# Output.net
KiCad netlist of a schematic drawn in Altium Designer
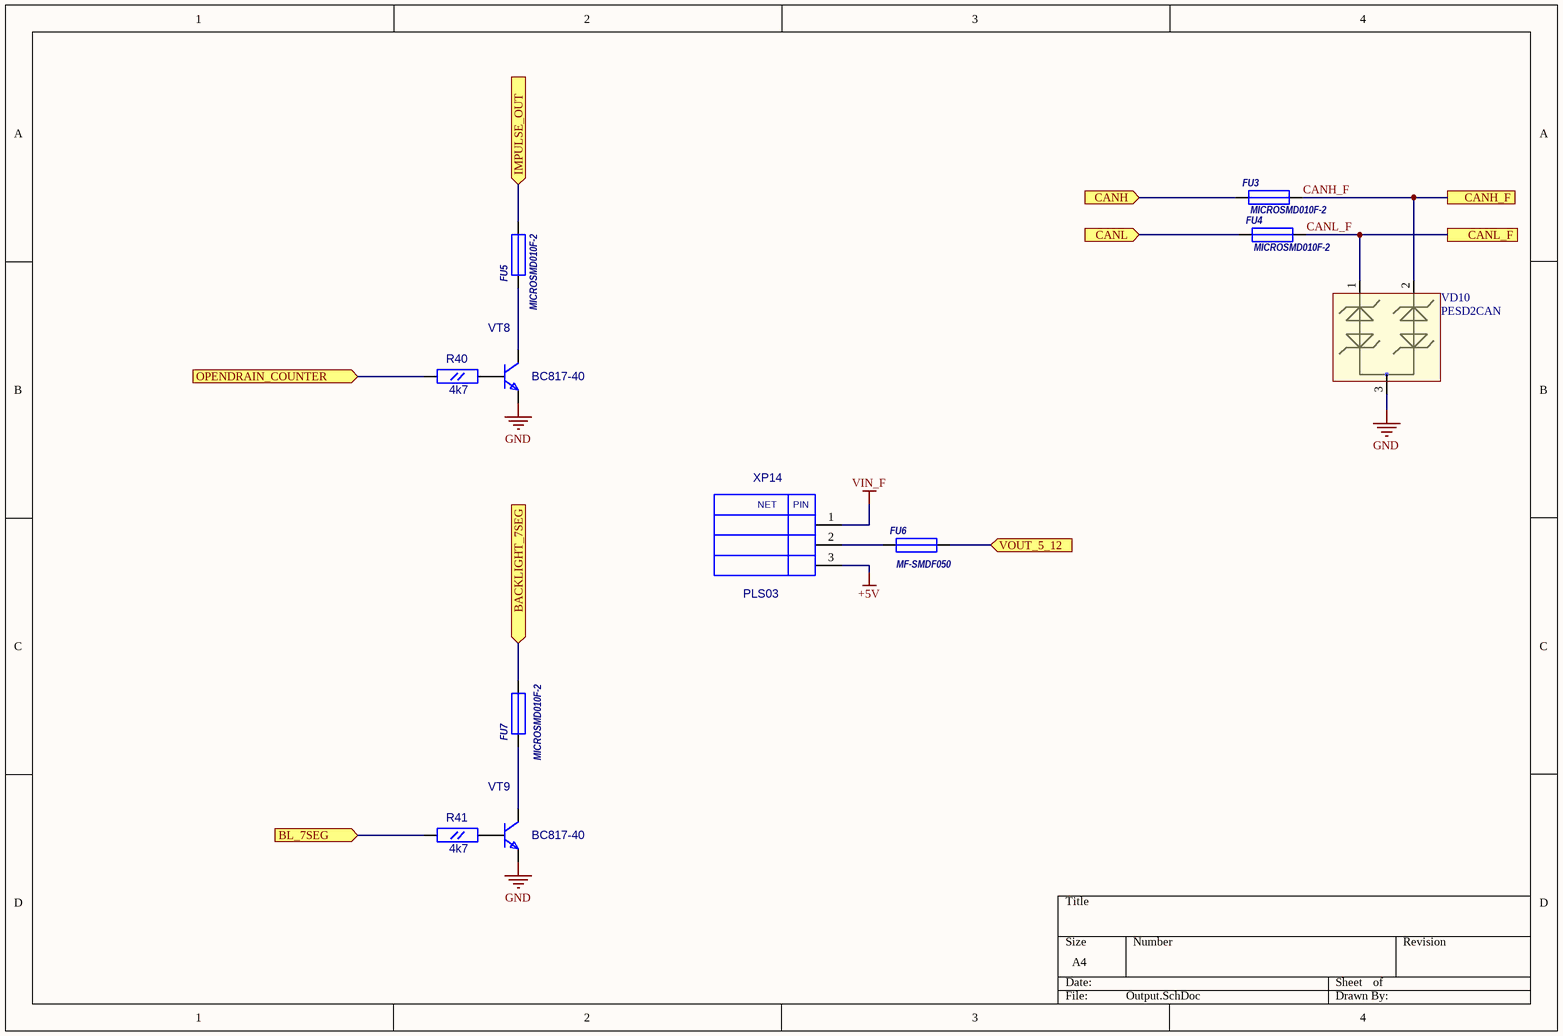
[diagram p0: Output.SchDoc]

(export (version "E")
  (design (tool "Eeschema 10.0.6"))
  (components
    (comp (ref "FU3")
      (value "MICROSMD010F-2")
      (footprint "RC1210")
      (description "MICROSMD")
      (libsource (lib "gprs_modem_2") (part "MICROSMD"))
    )
    (comp (ref "FU4")
      (value "MICROSMD010F-2")
      (footprint "RC1210")
      (description "MICROSMD")
      (libsource (lib "gprs_modem_2") (part "MICROSMD"))
    )
    (comp (ref "FU5")
      (value "MICROSMD010F-2")
      (footprint "RC1210")
      (description "MICROSMD")
      (libsource (lib "gprs_modem_2") (part "MICROSMD"))
    )
    (comp (ref "FU6")
      (value "MF-SMDF050")
      (footprint "MF-SMDF")
      (description "MF-SMDF")
      (libsource (lib "gprs_modem_2") (part "MF-SMDF"))
    )
    (comp (ref "FU7")
      (value "MICROSMD010F-2")
      (footprint "RC1210")
      (description "MICROSMD")
      (libsource (lib "gprs_modem_2") (part "MICROSMD"))
    )
    (comp (ref "R40")
      (value "4k7")
      (footprint "RC0603")
      (description "RC0603")
      (libsource (lib "gprs_modem_2") (part "RC0603"))
    )
    (comp (ref "R41")
      (value "4k7")
      (footprint "RC0603")
      (description "RC0603")
      (libsource (lib "gprs_modem_2") (part "RC0603"))
    )
    (comp (ref "VD10")
      (value "PESD2CAN")
      (footprint "SOT-23(123)")
      (description "TVS for CAN")
      (libsource (lib "gprs_modem_2") (part "PESD2CAN"))
    )
    (comp (ref "VT8")
      (value "BC817-40")
      (footprint "SOT-23(123)")
      (description "NPN 500ma transistor")
      (libsource (lib "gprs_modem_2") (part "BC846BLT1"))
    )
    (comp (ref "VT9")
      (value "BC817-40")
      (footprint "SOT-23(123)")
      (description "NPN 500ma transistor")
      (libsource (lib "gprs_modem_2") (part "BC846BLT1"))
    )
    (comp (ref "XP14") (value "PLS03") (footprint "PLS-03") (libsource (lib "gprs_modem_2") (part "PLS03")))
  )
  (nets
    (net (code "1") (name "+5V") (class "Default")
      (node (ref "XP14") (pin "3") (pinfunction "3_3") (pintype "passive"))
    )
    (net (code "2") (name "/BACKLIGHT_7SEG") (class "Default")
      (node (ref "FU7") (pin "2") (pintype "passive"))
    )
    (net (code "3") (name "/BL_7SEG") (class "Default")
      (node (ref "R41") (pin "1") (pinfunction "A_1") (pintype "passive"))
    )
    (net (code "4") (name "/CANH") (class "Default") (node (ref "FU3") (pin "1") (pintype "passive")))
    (net (code "5") (name "/CANH_F") (class "Default")
      (node (ref "FU3") (pin "2") (pintype "passive"))
      (node (ref "VD10") (pin "2") (pinfunction "2_2") (pintype "passive"))
    )
    (net (code "6") (name "/CANL") (class "Default") (node (ref "FU4") (pin "1") (pintype "passive")))
    (net (code "7") (name "/CANL_F") (class "Default")
      (node (ref "FU4") (pin "2") (pintype "passive"))
      (node (ref "VD10") (pin "1") (pinfunction "1_1") (pintype "passive"))
    )
    (net (code "8") (name "/IMPULSE_OUT") (class "Default") (node (ref "FU5") (pin "2") (pintype "passive")))
    (net (code "9") (name "/OPENDRAIN_COUNTER") (class "Default")
      (node (ref "R40") (pin "1") (pinfunction "A_1") (pintype "passive"))
    )
    (net (code "10") (name "/VOUT_5_12") (class "Default") (node (ref "FU6") (pin "2") (pintype "passive")))
    (net (code "11") (name "GND") (class "Default")
      (node (ref "VD10") (pin "3") (pinfunction "3_3") (pintype "passive"))
      (node (ref "VT8") (pin "2") (pinfunction "E_2") (pintype "passive"))
      (node (ref "VT9") (pin "2") (pinfunction "E_2") (pintype "passive"))
    )
    (net (code "12") (name "Net-(FU6-Pad1)") (class "Default")
      (node (ref "FU6") (pin "1") (pintype "passive"))
      (node (ref "XP14") (pin "2") (pinfunction "2_2") (pintype "passive"))
    )
    (net (code "13") (name "Net-(R40-B)") (class "Default")
      (node (ref "R40") (pin "2") (pinfunction "B_2") (pintype "passive"))
      (node (ref "VT8") (pin "1") (pinfunction "B_1") (pintype "passive"))
    )
    (net (code "14") (name "Net-(R41-B)") (class "Default")
      (node (ref "R41") (pin "2") (pinfunction "B_2") (pintype "passive"))
      (node (ref "VT9") (pin "1") (pinfunction "B_1") (pintype "passive"))
    )
    (net (code "15") (name "Net-(VT8-C)") (class "Default")
      (node (ref "FU5") (pin "1") (pintype "passive"))
      (node (ref "VT8") (pin "3") (pinfunction "C_3") (pintype "passive"))
    )
    (net (code "16") (name "Net-(VT9-C)") (class "Default")
      (node (ref "FU7") (pin "1") (pintype "passive"))
      (node (ref "VT9") (pin "3") (pinfunction "C_3") (pintype "passive"))
    )
    (net (code "17") (name "VIN_F") (class "Default")
      (node (ref "XP14") (pin "1") (pinfunction "1_1") (pintype "passive"))
    )
  )
)
